# Arduino_Nano_SD_Serayu_2024.net
KiCad netlist of a schematic drawn in EAGLE
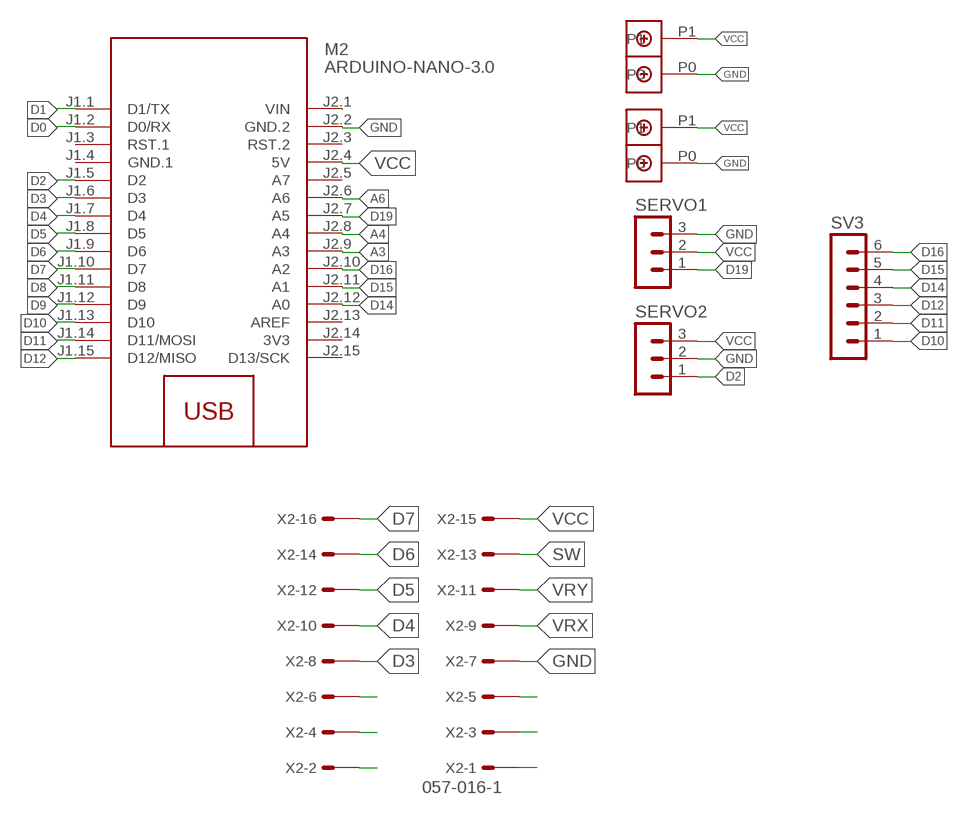
[diagram p0: schematic, sheet 1]

(export (version "E")
  (design (tool "Eeschema 10.0.6"))
  (components
    (comp (ref "M2")
      (value "ARDUINO-NANO-3.0")
      (footprint "eagle-import:ARDUINO-NANO-3.0")
      (libsource (lib "eagle-import") (part "ARDUINO-NANO-3.0"))
    )
    (comp (ref "SERVO1")
      (value "MA03-1")
      (footprint "eagle-import:MA03-1")
      (libsource (lib "eagle-import") (part "MA03-1"))
    )
    (comp (ref "SERVO2")
      (value "MA03-1")
      (footprint "eagle-import:MA03-1")
      (libsource (lib "eagle-import") (part "MA03-1"))
    )
    (comp (ref "SV3")
      (value "MA06-1")
      (footprint "eagle-import:MA06-1")
      (libsource (lib "eagle-import") (part "MA06-1"))
    )
    (comp (ref "U$1")
      (value "DBCONN-1X2")
      (footprint "eagle-import:DBCONN-1X2")
      (libsource (lib "eagle-import") (part "DBCONN-1X2"))
    )
    (comp (ref "U$2")
      (value "DBCONN-1X2")
      (footprint "eagle-import:DBCONN-1X2")
      (libsource (lib "eagle-import") (part "DBCONN-1X2"))
    )
    (comp (ref "X2")
      (value "057-016-1")
      (footprint "eagle-import:057-016-1")
      (libsource (lib "eagle-import") (part "057-016-1"))
    )
  )
  (nets
    (net (code "1") (name "/3V3") (class "Default")
      (node (ref "M2") (pin "J2.14") (pinfunction "3V3_J2.14") (pintype "power_in"))
    )
    (net (code "2") (name "/GND.1") (class "Default")
      (node (ref "M2") (pin "J1.4") (pinfunction "GND.1_J1.4") (pintype "power_in"))
    )
    (net (code "3") (name "A3") (class "Default")
      (node (ref "M2") (pin "J2.9") (pinfunction "A3_J2.9") (pintype "bidirectional"))
    )
    (net (code "4") (name "A4") (class "Default")
      (node (ref "M2") (pin "J2.8") (pinfunction "A4_J2.8") (pintype "bidirectional"))
    )
    (net (code "5") (name "A6") (class "Default")
      (node (ref "M2") (pin "J2.6") (pinfunction "A6_J2.6") (pintype "bidirectional"))
    )
    (net (code "6") (name "D0") (class "Default")
      (node (ref "M2") (pin "J1.2") (pinfunction "D0/RX_J1.2") (pintype "bidirectional"))
    )
    (net (code "7") (name "D1") (class "Default")
      (node (ref "M2") (pin "J1.1") (pinfunction "D1/TX_J1.1") (pintype "bidirectional"))
    )
    (net (code "8") (name "D2") (class "Default")
      (node (ref "M2") (pin "J1.5") (pinfunction "D2_J1.5") (pintype "bidirectional"))
      (node (ref "SERVO2") (pin "1") (pinfunction "1_1") (pintype "passive"))
    )
    (net (code "9") (name "D3") (class "Default")
      (node (ref "M2") (pin "J1.6") (pinfunction "D3_J1.6") (pintype "bidirectional"))
      (node (ref "X2") (pin "8") (pinfunction "S_8") (pintype "passive"))
    )
    (net (code "10") (name "D4") (class "Default")
      (node (ref "M2") (pin "J1.7") (pinfunction "D4_J1.7") (pintype "bidirectional"))
      (node (ref "X2") (pin "10") (pinfunction "S_10") (pintype "passive"))
    )
    (net (code "11") (name "D5") (class "Default")
      (node (ref "M2") (pin "J1.8") (pinfunction "D5_J1.8") (pintype "bidirectional"))
      (node (ref "X2") (pin "12") (pinfunction "S_12") (pintype "passive"))
    )
    (net (code "12") (name "D6") (class "Default")
      (node (ref "M2") (pin "J1.9") (pinfunction "D6_J1.9") (pintype "bidirectional"))
      (node (ref "X2") (pin "14") (pinfunction "S_14") (pintype "passive"))
    )
    (net (code "13") (name "D7") (class "Default")
      (node (ref "M2") (pin "J1.10") (pinfunction "D7_J1.10") (pintype "bidirectional"))
      (node (ref "X2") (pin "16") (pinfunction "S_16") (pintype "passive"))
    )
    (net (code "14") (name "D8") (class "Default")
      (node (ref "M2") (pin "J1.11") (pinfunction "D8_J1.11") (pintype "bidirectional"))
    )
    (net (code "15") (name "D9") (class "Default")
      (node (ref "M2") (pin "J1.12") (pinfunction "D9_J1.12") (pintype "bidirectional"))
    )
    (net (code "16") (name "D10") (class "Default")
      (node (ref "M2") (pin "J1.13") (pinfunction "D10_J1.13") (pintype "bidirectional"))
      (node (ref "SV3") (pin "1") (pinfunction "1_1") (pintype "passive"))
    )
    (net (code "17") (name "D11") (class "Default")
      (node (ref "M2") (pin "J1.14") (pinfunction "D11/MOSI_J1.14") (pintype "bidirectional"))
      (node (ref "SV3") (pin "2") (pinfunction "2_2") (pintype "passive"))
    )
    (net (code "18") (name "D12") (class "Default")
      (node (ref "M2") (pin "J1.15") (pinfunction "D12/MISO_J1.15") (pintype "bidirectional"))
      (node (ref "SV3") (pin "3") (pinfunction "3_3") (pintype "passive"))
    )
    (net (code "19") (name "D14") (class "Default")
      (node (ref "M2") (pin "J2.12") (pinfunction "A0_J2.12") (pintype "bidirectional"))
      (node (ref "SV3") (pin "4") (pinfunction "4_4") (pintype "passive"))
    )
    (net (code "20") (name "D15") (class "Default")
      (node (ref "M2") (pin "J2.11") (pinfunction "A1_J2.11") (pintype "bidirectional"))
      (node (ref "SV3") (pin "5") (pinfunction "5_5") (pintype "passive"))
    )
    (net (code "21") (name "D16") (class "Default")
      (node (ref "M2") (pin "J2.10") (pinfunction "A2_J2.10") (pintype "bidirectional"))
      (node (ref "SV3") (pin "6") (pinfunction "6_6") (pintype "passive"))
    )
    (net (code "22") (name "D19") (class "Default")
      (node (ref "M2") (pin "J2.7") (pinfunction "A5_J2.7") (pintype "bidirectional"))
      (node (ref "SERVO1") (pin "1") (pinfunction "1_1") (pintype "passive"))
    )
    (net (code "23") (name "GND") (class "Default")
      (node (ref "M2") (pin "J2.2") (pinfunction "GND.2_J2.2") (pintype "power_in"))
      (node (ref "SERVO1") (pin "3") (pinfunction "3_3") (pintype "passive"))
      (node (ref "SERVO2") (pin "2") (pinfunction "2_2") (pintype "passive"))
      (node (ref "U$1") (pin "P0") (pinfunction "P0_P0") (pintype "bidirectional"))
      (node (ref "U$2") (pin "P0") (pinfunction "P0_P0") (pintype "bidirectional"))
      (node (ref "X2") (pin "7") (pinfunction "S_7") (pintype "passive"))
    )
    (net (code "24") (name "SW") (class "Default")
      (node (ref "X2") (pin "13") (pinfunction "S_13") (pintype "passive"))
    )
    (net (code "25") (name "VCC") (class "Default")
      (node (ref "M2") (pin "J2.1") (pinfunction "VIN_J2.1") (pintype "power_in"))
      (node (ref "M2") (pin "J2.4") (pinfunction "5V_J2.4") (pintype "power_in"))
      (node (ref "SERVO1") (pin "2") (pinfunction "2_2") (pintype "passive"))
      (node (ref "SERVO2") (pin "3") (pinfunction "3_3") (pintype "passive"))
      (node (ref "U$1") (pin "P1") (pinfunction "P1_P1") (pintype "bidirectional"))
      (node (ref "U$2") (pin "P1") (pinfunction "P1_P1") (pintype "bidirectional"))
      (node (ref "X2") (pin "15") (pinfunction "S_15") (pintype "passive"))
    )
    (net (code "26") (name "VRX") (class "Default")
      (node (ref "X2") (pin "9") (pinfunction "S_9") (pintype "passive"))
    )
    (net (code "27") (name "VRY") (class "Default")
      (node (ref "X2") (pin "11") (pinfunction "S_11") (pintype "passive"))
    )
    (net (code "28") (name "unconnected-(M2-A7-PadJ2.5)") (class "Default")
      (node (ref "M2") (pin "J2.5") (pinfunction "A7_J2.5") (pintype "bidirectional"))
    )
    (net (code "29") (name "unconnected-(M2-AREF-PadJ2.13)") (class "Default")
      (node (ref "M2") (pin "J2.13") (pinfunction "AREF_J2.13") (pintype "bidirectional"))
    )
    (net (code "30") (name "unconnected-(M2-D13{slash}SCK-PadJ2.15)") (class "Default")
      (node (ref "M2") (pin "J2.15") (pinfunction "D13/SCK_J2.15") (pintype "bidirectional"))
    )
    (net (code "31") (name "unconnected-(M2-RST.1-PadJ1.3)") (class "Default")
      (node (ref "M2") (pin "J1.3") (pinfunction "RST.1_J1.3") (pintype "bidirectional"))
    )
    (net (code "32") (name "unconnected-(M2-RST.2-PadJ2.3)") (class "Default")
      (node (ref "M2") (pin "J2.3") (pinfunction "RST.2_J2.3") (pintype "bidirectional"))
    )
    (net (code "33") (name "unconnected-(X2A-S-Pad1)") (class "Default")
      (node (ref "X2") (pin "1") (pinfunction "S_1") (pintype "passive"))
    )
    (net (code "34") (name "unconnected-(X2I-S-Pad2)") (class "Default")
      (node (ref "X2") (pin "2") (pinfunction "S_2") (pintype "passive"))
    )
    (net (code "35") (name "unconnected-(X2J-S-Pad3)") (class "Default")
      (node (ref "X2") (pin "3") (pinfunction "S_3") (pintype "passive"))
    )
    (net (code "36") (name "unconnected-(X2K-S-Pad4)") (class "Default")
      (node (ref "X2") (pin "4") (pinfunction "S_4") (pintype "passive"))
    )
    (net (code "37") (name "unconnected-(X2L-S-Pad5)") (class "Default")
      (node (ref "X2") (pin "5") (pinfunction "S_5") (pintype "passive"))
    )
    (net (code "38") (name "unconnected-(X2M-S-Pad6)") (class "Default")
      (node (ref "X2") (pin "6") (pinfunction "S_6") (pintype "passive"))
    )
  )
)
